# power_electronics6.net
KiCad netlist of a schematic drawn in EAGLE
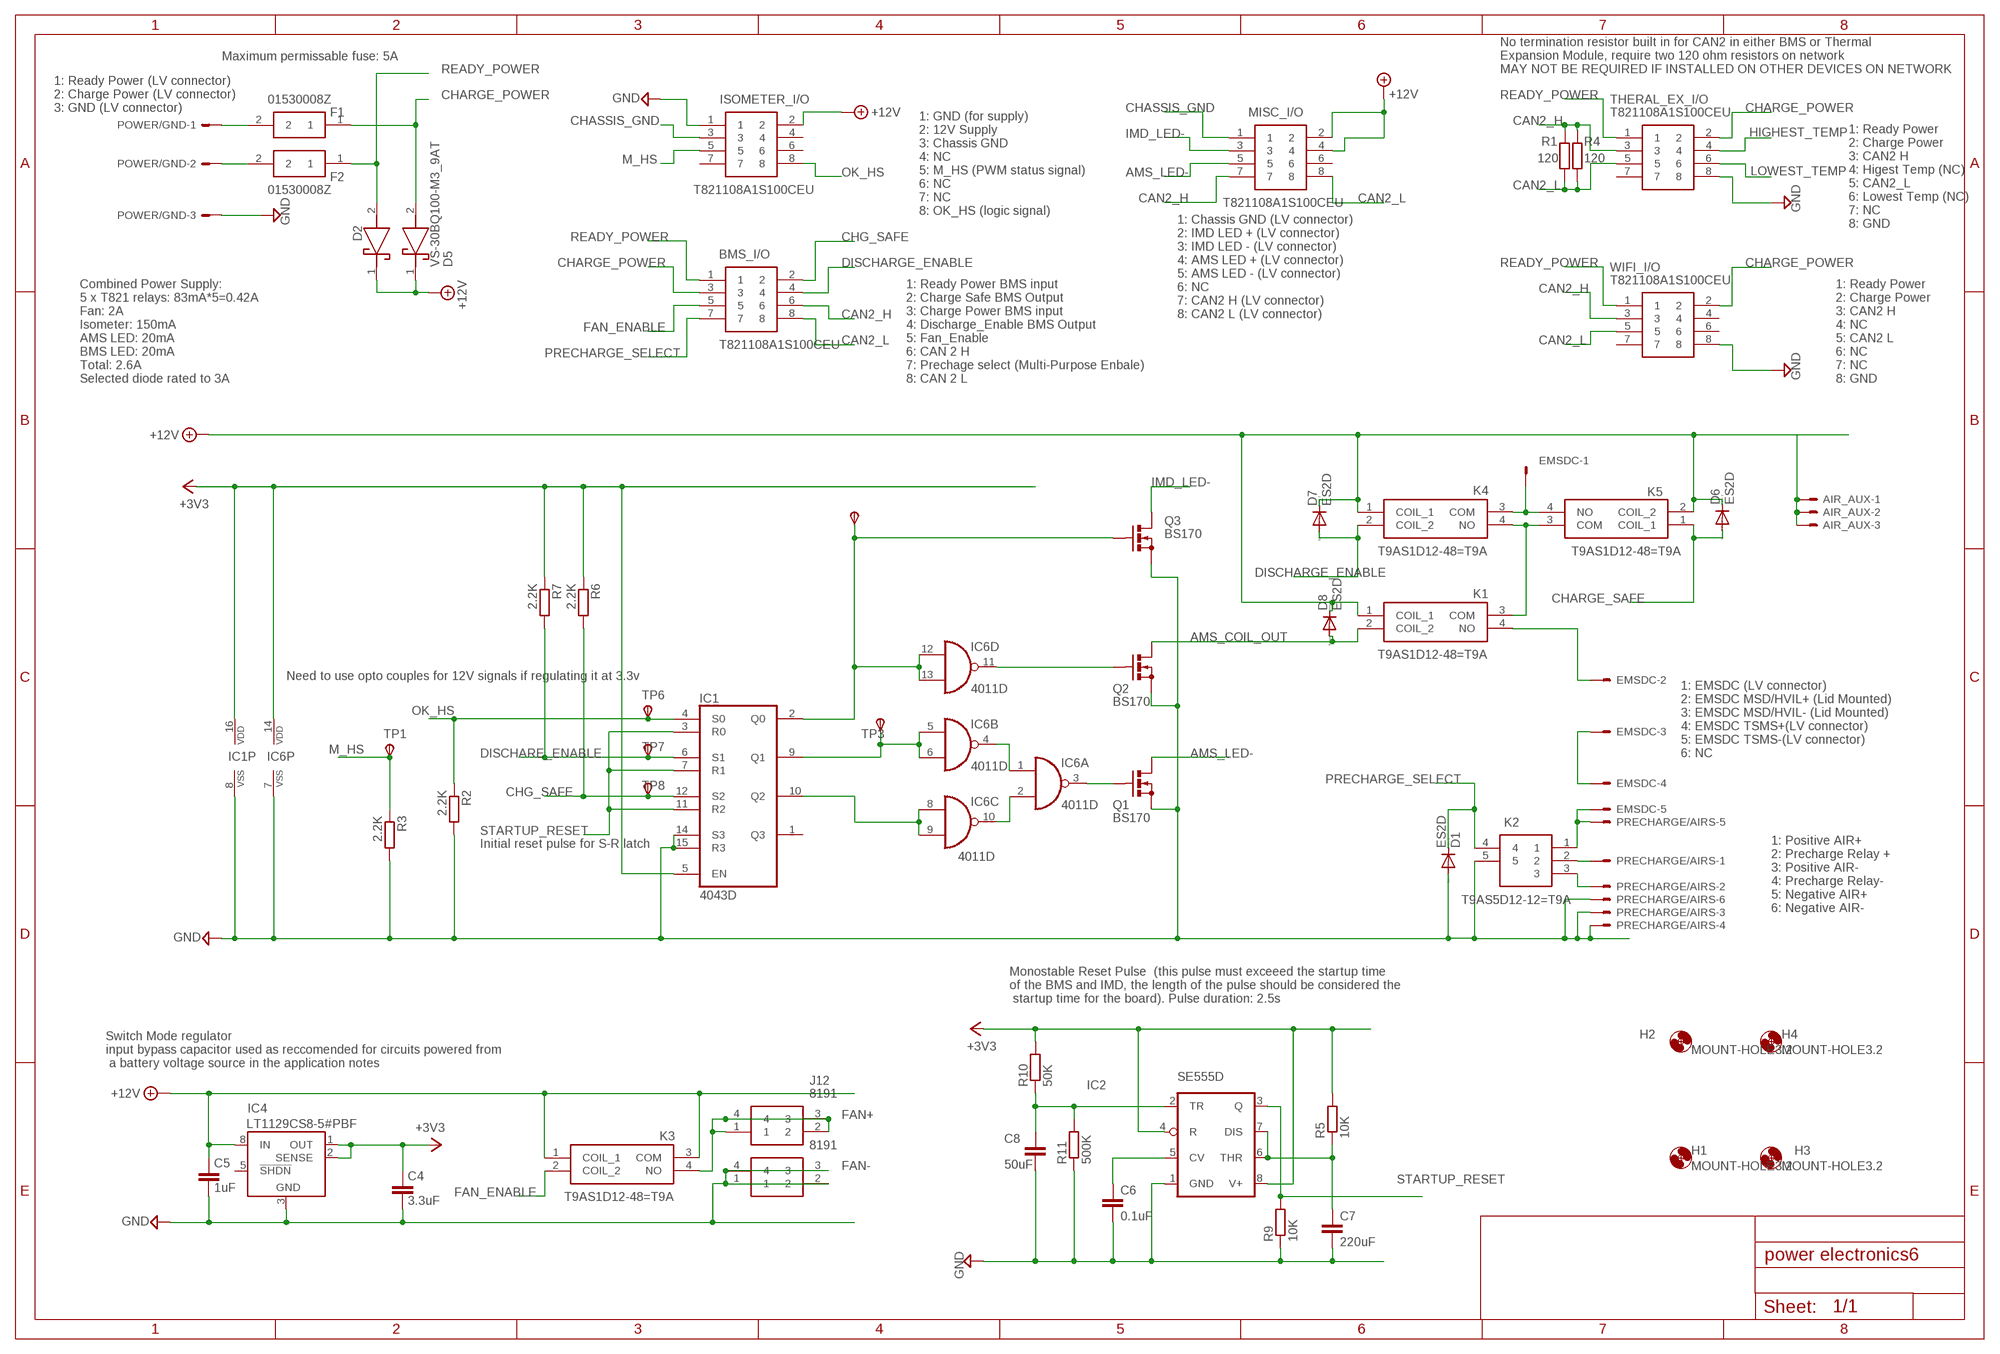
[diagram p0: schematic, sheet 1]

(export (version "E")
  (design (tool "Eeschema 10.0.6"))
  (components
    (comp (ref "AIR_AUX")
      (value "KK-156-3")
      (footprint "eagle-import:KK-156-3")
      (fields (field (name "MF") "MOLEX"))
      (libsource (lib "eagle-import") (part "KK-156-3"))
    )
    (comp (ref "BMS_I/O")
      (value "T821108A1S100CEU")
      (footprint "eagle-import:HDRV8W64P254_2X4_1778X895X915P")
      (fields (field (name "RS_PART_NUMBER") "8323569"))
      (libsource (lib "eagle-import") (part "T821108A1S100CEU"))
    )
    (comp (ref "C4")
      (value "3.3uF")
      (footprint "eagle-import:C1206")
      (libsource (lib "eagle-import") (part "C-EUC1206"))
    )
    (comp (ref "C5")
      (value "1uF")
      (footprint "eagle-import:C1206")
      (libsource (lib "eagle-import") (part "C-EUC1206"))
    )
    (comp (ref "C6")
      (value "0.1uF")
      (footprint "eagle-import:C1206")
      (libsource (lib "eagle-import") (part "C-EUC1206"))
    )
    (comp (ref "C7")
      (value "220uF")
      (footprint "eagle-import:C1206")
      (libsource (lib "eagle-import") (part "C-EUC1206"))
    )
    (comp (ref "C8")
      (value "50uF")
      (footprint "eagle-import:C1206")
      (libsource (lib "eagle-import") (part "C-EUC1206"))
    )
    (comp (ref "D1")
      (value "ES2D")
      (footprint "eagle-import:SMB")
      (libsource (lib "eagle-import") (part "ES2D"))
    )
    (comp (ref "D2")
      (value "VS-30BQ100-M3_9AT")
      (footprint "eagle-import:DIOM7959X262N")
      (fields
        (field (name "MANUFACTURER_PART_NUMBER") "VS-30BQ100-M3/9AT")
        (field (name "MOUSER_PART_NUMBER") "78-VS-30BQ100-M39AT")
      )
      (libsource (lib "eagle-import") (part "VS-30BQ100-M3_9AT"))
    )
    (comp (ref "D5")
      (value "VS-30BQ100-M3_9AT")
      (footprint "eagle-import:DIOM7959X262N")
      (fields
        (field (name "MANUFACTURER_PART_NUMBER") "VS-30BQ100-M3/9AT")
        (field (name "MOUSER_PART_NUMBER") "78-VS-30BQ100-M39AT")
      )
      (libsource (lib "eagle-import") (part "VS-30BQ100-M3_9AT"))
    )
    (comp (ref "D6")
      (value "ES2D")
      (footprint "eagle-import:SMB")
      (libsource (lib "eagle-import") (part "ES2D"))
    )
    (comp (ref "D7")
      (value "ES2D")
      (footprint "eagle-import:SMB")
      (libsource (lib "eagle-import") (part "ES2D"))
    )
    (comp (ref "D8")
      (value "ES2D")
      (footprint "eagle-import:SMB")
      (libsource (lib "eagle-import") (part "ES2D"))
    )
    (comp (ref "EMSDC")
      (value "KK-156-6")
      (footprint "eagle-import:KK-156-6")
      (fields (field (name "MF") "MOLEX"))
      (libsource (lib "eagle-import") (part "KK-156-6"))
    )
    (comp (ref "F1")
      (value "01530008Z")
      (footprint "eagle-import:01530008")
      (fields (field (name "RS_PART_NUMBER") "3607317"))
      (libsource (lib "eagle-import") (part "01530008Z"))
    )
    (comp (ref "F2")
      (value "01530008Z")
      (footprint "eagle-import:01530008")
      (fields (field (name "RS_PART_NUMBER") "3607317"))
      (libsource (lib "eagle-import") (part "01530008Z"))
    )
    (comp (ref "FAN-")
      (value "8191")
      (footprint "eagle-import:8191")
      (fields (field (name "MOUSER_PART_NUMBER") "534-8191") (field (name "RS_PART_NUMBER") "1194011"))
      (libsource (lib "eagle-import") (part "8191"))
    )
    (comp (ref "H1")
      (value "MOUNT-HOLE3.2")
      (footprint "eagle-import:3,2")
      (libsource (lib "eagle-import") (part "MOUNT-HOLE3.2"))
    )
    (comp (ref "H2")
      (value "MOUNT-HOLE3.2")
      (footprint "eagle-import:3,2")
      (libsource (lib "eagle-import") (part "MOUNT-HOLE3.2"))
    )
    (comp (ref "H3")
      (value "MOUNT-HOLE3.2")
      (footprint "eagle-import:3,2")
      (libsource (lib "eagle-import") (part "MOUNT-HOLE3.2"))
    )
    (comp (ref "H4")
      (value "MOUNT-HOLE3.2")
      (footprint "eagle-import:3,2")
      (libsource (lib "eagle-import") (part "MOUNT-HOLE3.2"))
    )
    (comp (ref "IC1")
      (value "4043D")
      (footprint "eagle-import:SO16")
      (libsource (lib "eagle-import") (part "4043D"))
    )
    (comp (ref "IC2")
      (value "SE555D")
      (footprint "eagle-import:SO08")
      (libsource (lib "eagle-import") (part "555DSE"))
    )
    (comp (ref "IC4")
      (value "LT1129CS8")
      (footprint "eagle-import:SOIC8")
      (fields (field (name "MPN") "LT1129CS8-5#PBF"))
      (libsource (lib "eagle-import") (part "LT1129CS8"))
    )
    (comp (ref "IC6")
      (value "4011D")
      (footprint "eagle-import:SO14")
      (libsource (lib "eagle-import") (part "4011D"))
    )
    (comp (ref "ISOMETER_I/O")
      (value "T821108A1S100CEU")
      (footprint "eagle-import:HDRV8W64P254_2X4_1778X895X915P")
      (fields (field (name "RS_PART_NUMBER") "8323569"))
      (libsource (lib "eagle-import") (part "T821108A1S100CEU"))
    )
    (comp (ref "J12")
      (value "8191")
      (footprint "eagle-import:8191")
      (fields (field (name "MOUSER_PART_NUMBER") "534-8191") (field (name "RS_PART_NUMBER") "1194011"))
      (libsource (lib "eagle-import") (part "8191"))
    )
    (comp (ref "K1")
      (value "T9AS1D12-48=T9A")
      (footprint "eagle-import:T9AS1D1248T9A")
      (fields (field (name "RS_PART_NUMBER") "6802534P"))
      (libsource (lib "eagle-import") (part "T9AS1D12-48=T9A"))
    )
    (comp (ref "K2")
      (value "T9AS5D12-12=T9A")
      (footprint "eagle-import:T9AS1D12")
      (fields (field (name "RS_PART_NUMBER") "6802528"))
      (libsource (lib "eagle-import") (part "T9AS5D12-12=T9A"))
    )
    (comp (ref "K3")
      (value "T9AS1D12-48=T9A")
      (footprint "eagle-import:T9AS1D1248T9A")
      (fields (field (name "RS_PART_NUMBER") "6802534P"))
      (libsource (lib "eagle-import") (part "T9AS1D12-48=T9A"))
    )
    (comp (ref "K4")
      (value "T9AS1D12-48=T9A")
      (footprint "eagle-import:T9AS1D1248T9A")
      (fields (field (name "RS_PART_NUMBER") "6802534P"))
      (libsource (lib "eagle-import") (part "T9AS1D12-48=T9A"))
    )
    (comp (ref "K5")
      (value "T9AS1D12-48=T9A")
      (footprint "eagle-import:T9AS1D1248T9A")
      (fields (field (name "RS_PART_NUMBER") "6802534P"))
      (libsource (lib "eagle-import") (part "T9AS1D12-48=T9A"))
    )
    (comp (ref "MISC_I/O")
      (value "T821108A1S100CEU")
      (footprint "eagle-import:HDRV8W64P254_2X4_1778X895X915P")
      (fields (field (name "RS_PART_NUMBER") "8323569"))
      (libsource (lib "eagle-import") (part "T821108A1S100CEU"))
    )
    (comp (ref "POWER/GND")
      (value "KK-156-3")
      (footprint "eagle-import:KK-156-3")
      (fields (field (name "MF") "MOLEX"))
      (libsource (lib "eagle-import") (part "KK-156-3"))
    )
    (comp (ref "PRECHARGE/AIRS")
      (value "KK-156-6")
      (footprint "eagle-import:KK-156-6")
      (fields (field (name "MF") "MOLEX"))
      (libsource (lib "eagle-import") (part "KK-156-6"))
    )
    (comp (ref "Q1")
      (value "BS170")
      (footprint "eagle-import:SOT54E")
      (libsource (lib "eagle-import") (part "BS170"))
    )
    (comp (ref "Q2")
      (value "BS170")
      (footprint "eagle-import:SOT54E")
      (libsource (lib "eagle-import") (part "BS170"))
    )
    (comp (ref "Q3")
      (value "BS170")
      (footprint "eagle-import:SOT54E")
      (libsource (lib "eagle-import") (part "BS170"))
    )
    (comp (ref "R1")
      (value "120")
      (footprint "eagle-import:R1206")
      (libsource (lib "eagle-import") (part "R-EU_R1206"))
    )
    (comp (ref "R2")
      (value "2.2K")
      (footprint "eagle-import:R1206")
      (libsource (lib "eagle-import") (part "R-EU_R1206"))
    )
    (comp (ref "R3")
      (value "2.2K")
      (footprint "eagle-import:R1206")
      (libsource (lib "eagle-import") (part "R-EU_R1206"))
    )
    (comp (ref "R4")
      (value "120")
      (footprint "eagle-import:R1206")
      (libsource (lib "eagle-import") (part "R-EU_R1206"))
    )
    (comp (ref "R5")
      (value "10K")
      (footprint "eagle-import:R1206")
      (libsource (lib "eagle-import") (part "R-EU_R1206"))
    )
    (comp (ref "R6")
      (value "2.2K")
      (footprint "eagle-import:R1206")
      (libsource (lib "eagle-import") (part "R-EU_R1206"))
    )
    (comp (ref "R7")
      (value "2.2K")
      (footprint "eagle-import:R1206")
      (libsource (lib "eagle-import") (part "R-EU_R1206"))
    )
    (comp (ref "R9")
      (value "10K")
      (footprint "eagle-import:R1206")
      (libsource (lib "eagle-import") (part "R-EU_R1206"))
    )
    (comp (ref "R10")
      (value "50K")
      (footprint "eagle-import:R1206")
      (libsource (lib "eagle-import") (part "R-EU_R1206"))
    )
    (comp (ref "R11")
      (value "500K")
      (footprint "eagle-import:R1206")
      (libsource (lib "eagle-import") (part "R-EU_R1206"))
    )
    (comp (ref "THERAL_EX_I/O")
      (value "T821108A1S100CEU")
      (footprint "eagle-import:HDRV8W64P254_2X4_1778X895X915P")
      (fields (field (name "RS_PART_NUMBER") "8323569"))
      (libsource (lib "eagle-import") (part "T821108A1S100CEU"))
    )
    (comp (ref "TP1")
      (value "TPSPAD1-17")
      (footprint "eagle-import:P1-17")
      (libsource (lib "eagle-import") (part "TPSPAD1-17"))
    )
    (comp (ref "TP2")
      (value "TPSPAD1-17")
      (footprint "eagle-import:P1-17")
      (libsource (lib "eagle-import") (part "TPSPAD1-17"))
    )
    (comp (ref "TP3")
      (value "TPSPAD1-17")
      (footprint "eagle-import:P1-17")
      (libsource (lib "eagle-import") (part "TPSPAD1-17"))
    )
    (comp (ref "TP6")
      (value "TPSPAD1-17")
      (footprint "eagle-import:P1-17")
      (libsource (lib "eagle-import") (part "TPSPAD1-17"))
    )
    (comp (ref "TP7")
      (value "TPSPAD1-17")
      (footprint "eagle-import:P1-17")
      (libsource (lib "eagle-import") (part "TPSPAD1-17"))
    )
    (comp (ref "TP8")
      (value "TPSPAD1-17")
      (footprint "eagle-import:P1-17")
      (libsource (lib "eagle-import") (part "TPSPAD1-17"))
    )
    (comp (ref "WIFI_I/O")
      (value "T821108A1S100CEU")
      (footprint "eagle-import:HDRV8W64P254_2X4_1778X895X915P")
      (fields (field (name "RS_PART_NUMBER") "8323569"))
      (libsource (lib "eagle-import") (part "T821108A1S100CEU"))
    )
  )
  (nets
    (net (code "1") (name "+3V3") (class "Default")
      (node (ref "C4") (pin "1") (pinfunction "1_1") (pintype "passive"))
      (node (ref "IC1") (pin "16") (pinfunction "VDD_16") (pintype "power_in"))
      (node (ref "IC1") (pin "5") (pinfunction "EN_5") (pintype "input"))
      (node (ref "IC2") (pin "4") (pinfunction "R_4") (pintype "input"))
      (node (ref "IC2") (pin "8") (pinfunction "V+_8") (pintype "power_in"))
      (node (ref "IC4") (pin "1") (pinfunction "OUT_1") (pintype "output"))
      (node (ref "IC4") (pin "2") (pinfunction "SENSE_2") (pintype "input"))
      (node (ref "IC6") (pin "14") (pinfunction "VDD_14") (pintype "power_in"))
      (node (ref "R10") (pin "2") (pinfunction "2_2") (pintype "passive"))
      (node (ref "R5") (pin "2") (pinfunction "2_2") (pintype "passive"))
      (node (ref "R6") (pin "1") (pinfunction "1_1") (pintype "passive"))
      (node (ref "R7") (pin "1") (pinfunction "1_1") (pintype "passive"))
    )
    (net (code "2") (name "+12V") (class "Default")
      (node (ref "AIR_AUX") (pin "1") (pinfunction "S_1") (pintype "passive"))
      (node (ref "AIR_AUX") (pin "2") (pinfunction "S_2") (pintype "passive"))
      (node (ref "AIR_AUX") (pin "3") (pinfunction "S_3") (pintype "passive"))
      (node (ref "C5") (pin "1") (pinfunction "1_1") (pintype "passive"))
      (node (ref "D2") (pin "1") (pinfunction "K_1") (pintype "bidirectional"))
      (node (ref "D5") (pin "1") (pinfunction "K_1") (pintype "bidirectional"))
      (node (ref "D6") (pin "C") (pinfunction "C_C") (pintype "passive"))
      (node (ref "D7") (pin "C") (pinfunction "C_C") (pintype "passive"))
      (node (ref "D8") (pin "C") (pinfunction "C_C") (pintype "passive"))
      (node (ref "IC4") (pin "8") (pinfunction "IN_8") (pintype "input"))
      (node (ref "ISOMETER_I/O") (pin "2") (pinfunction "2_2") (pintype "bidirectional"))
      (node (ref "K1") (pin "1") (pinfunction "COIL_1_1") (pintype "bidirectional"))
      (node (ref "K3") (pin "1") (pinfunction "COIL_1_1") (pintype "bidirectional"))
      (node (ref "K3") (pin "3") (pinfunction "COM_3") (pintype "bidirectional"))
      (node (ref "K4") (pin "1") (pinfunction "COIL_1_1") (pintype "bidirectional"))
      (node (ref "K5") (pin "2") (pinfunction "COIL_2_2") (pintype "bidirectional"))
      (node (ref "MISC_I/O") (pin "2") (pinfunction "2_2") (pintype "bidirectional"))
      (node (ref "MISC_I/O") (pin "4") (pinfunction "4_4") (pintype "bidirectional"))
    )
    (net (code "3") (name "/AMS_COIL_OUT") (class "Default")
      (node (ref "D8") (pin "A") (pinfunction "A_A") (pintype "passive"))
      (node (ref "K1") (pin "2") (pinfunction "COIL_2_2") (pintype "bidirectional"))
      (node (ref "Q2") (pin "D") (pinfunction "D_D") (pintype "passive"))
    )
    (net (code "4") (name "/AMS_LED-") (class "Default")
      (node (ref "MISC_I/O") (pin "5") (pinfunction "5_5") (pintype "bidirectional"))
      (node (ref "Q1") (pin "D") (pinfunction "D_D") (pintype "passive"))
    )
    (net (code "5") (name "/CAN2_H") (class "Default")
      (node (ref "BMS_I/O") (pin "6") (pinfunction "6_6") (pintype "bidirectional"))
      (node (ref "MISC_I/O") (pin "7") (pinfunction "7_7") (pintype "bidirectional"))
      (node (ref "R1") (pin "1") (pinfunction "1_1") (pintype "passive"))
      (node (ref "R4") (pin "1") (pinfunction "1_1") (pintype "passive"))
      (node (ref "THERAL_EX_I/O") (pin "3") (pinfunction "3_3") (pintype "bidirectional"))
      (node (ref "WIFI_I/O") (pin "3") (pinfunction "3_3") (pintype "bidirectional"))
    )
    (net (code "6") (name "/CAN2_L") (class "Default")
      (node (ref "BMS_I/O") (pin "8") (pinfunction "8_8") (pintype "bidirectional"))
      (node (ref "MISC_I/O") (pin "8") (pinfunction "8_8") (pintype "bidirectional"))
      (node (ref "R1") (pin "2") (pinfunction "2_2") (pintype "passive"))
      (node (ref "R4") (pin "2") (pinfunction "2_2") (pintype "passive"))
      (node (ref "THERAL_EX_I/O") (pin "5") (pinfunction "5_5") (pintype "bidirectional"))
      (node (ref "WIFI_I/O") (pin "5") (pinfunction "5_5") (pintype "bidirectional"))
    )
    (net (code "7") (name "/CHARGE_POWER") (class "Default")
      (node (ref "BMS_I/O") (pin "3") (pinfunction "3_3") (pintype "bidirectional"))
      (node (ref "D5") (pin "2") (pinfunction "A_2") (pintype "bidirectional"))
      (node (ref "F1") (pin "1") (pinfunction "1_1") (pintype "bidirectional"))
      (node (ref "THERAL_EX_I/O") (pin "2") (pinfunction "2_2") (pintype "bidirectional"))
      (node (ref "WIFI_I/O") (pin "2") (pinfunction "2_2") (pintype "bidirectional"))
    )
    (net (code "8") (name "/CHARGE_SAFE") (class "Default")
      (node (ref "D6") (pin "A") (pinfunction "A_A") (pintype "passive"))
      (node (ref "K5") (pin "1") (pinfunction "COIL_1_1") (pintype "bidirectional"))
    )
    (net (code "9") (name "/CHASSIS_GND") (class "Default")
      (node (ref "ISOMETER_I/O") (pin "3") (pinfunction "3_3") (pintype "bidirectional"))
      (node (ref "MISC_I/O") (pin "1") (pinfunction "1_1") (pintype "bidirectional"))
    )
    (net (code "10") (name "/CHG_SAFE") (class "Default")
      (node (ref "BMS_I/O") (pin "2") (pinfunction "2_2") (pintype "bidirectional"))
      (node (ref "IC1") (pin "12") (pinfunction "S2_12") (pintype "input"))
      (node (ref "R6") (pin "2") (pinfunction "2_2") (pintype "passive"))
      (node (ref "TP8") (pin "TP") (pinfunction "PP_TP") (pintype "input"))
    )
    (net (code "11") (name "/DISCHARE_ENABLE") (class "Default")
      (node (ref "IC1") (pin "6") (pinfunction "S1_6") (pintype "input"))
      (node (ref "R7") (pin "2") (pinfunction "2_2") (pintype "passive"))
      (node (ref "TP7") (pin "TP") (pinfunction "PP_TP") (pintype "input"))
    )
    (net (code "12") (name "/DISCHARGE_ENABLE") (class "Default")
      (node (ref "BMS_I/O") (pin "4") (pinfunction "4_4") (pintype "bidirectional"))
      (node (ref "D7") (pin "A") (pinfunction "A_A") (pintype "passive"))
      (node (ref "K4") (pin "2") (pinfunction "COIL_2_2") (pintype "bidirectional"))
    )
    (net (code "13") (name "/FAN+") (class "Default")
      (node (ref "J12") (pin "1") (pinfunction "1_1") (pintype "bidirectional"))
      (node (ref "J12") (pin "2") (pinfunction "2_2") (pintype "bidirectional"))
      (node (ref "J12") (pin "3") (pinfunction "3_3") (pintype "bidirectional"))
      (node (ref "J12") (pin "4") (pinfunction "4_4") (pintype "bidirectional"))
      (node (ref "K3") (pin "4") (pinfunction "NO_4") (pintype "bidirectional"))
    )
    (net (code "14") (name "/FAN_ENABLE") (class "Default")
      (node (ref "BMS_I/O") (pin "5") (pinfunction "5_5") (pintype "bidirectional"))
      (node (ref "K3") (pin "2") (pinfunction "COIL_2_2") (pintype "bidirectional"))
    )
    (net (code "15") (name "/HIGHEST_TEMP") (class "Default")
      (node (ref "THERAL_EX_I/O") (pin "4") (pinfunction "4_4") (pintype "bidirectional"))
    )
    (net (code "16") (name "/IMD_LED-") (class "Default")
      (node (ref "MISC_I/O") (pin "3") (pinfunction "3_3") (pintype "bidirectional"))
      (node (ref "Q3") (pin "D") (pinfunction "D_D") (pintype "passive"))
    )
    (net (code "17") (name "/LOWEST_TEMP") (class "Default")
      (node (ref "THERAL_EX_I/O") (pin "6") (pinfunction "6_6") (pintype "bidirectional"))
    )
    (net (code "18") (name "/M_HS") (class "Default")
      (node (ref "ISOMETER_I/O") (pin "5") (pinfunction "5_5") (pintype "bidirectional"))
      (node (ref "R3") (pin "1") (pinfunction "1_1") (pintype "passive"))
      (node (ref "TP1") (pin "TP") (pinfunction "PP_TP") (pintype "input"))
    )
    (net (code "19") (name "/OK_HS") (class "Default")
      (node (ref "IC1") (pin "4") (pinfunction "S0_4") (pintype "input"))
      (node (ref "ISOMETER_I/O") (pin "8") (pinfunction "8_8") (pintype "bidirectional"))
      (node (ref "R2") (pin "1") (pinfunction "1_1") (pintype "passive"))
      (node (ref "TP6") (pin "TP") (pinfunction "PP_TP") (pintype "input"))
    )
    (net (code "20") (name "/PRECHARGE_SELECT") (class "Default")
      (node (ref "BMS_I/O") (pin "7") (pinfunction "7_7") (pintype "bidirectional"))
      (node (ref "D1") (pin "C") (pinfunction "C_C") (pintype "passive"))
      (node (ref "K2") (pin "4") (pinfunction "4_4") (pintype "bidirectional"))
    )
    (net (code "21") (name "/READY_POWER") (class "Default")
      (node (ref "BMS_I/O") (pin "1") (pinfunction "1_1") (pintype "bidirectional"))
      (node (ref "D2") (pin "2") (pinfunction "A_2") (pintype "bidirectional"))
      (node (ref "F2") (pin "1") (pinfunction "1_1") (pintype "bidirectional"))
      (node (ref "THERAL_EX_I/O") (pin "1") (pinfunction "1_1") (pintype "bidirectional"))
      (node (ref "WIFI_I/O") (pin "1") (pinfunction "1_1") (pintype "bidirectional"))
    )
    (net (code "22") (name "/STARTUP_RESET") (class "Default")
      (node (ref "IC1") (pin "11") (pinfunction "R2_11") (pintype "input"))
      (node (ref "IC1") (pin "3") (pinfunction "R0_3") (pintype "input"))
      (node (ref "IC1") (pin "7") (pinfunction "R1_7") (pintype "input"))
      (node (ref "IC2") (pin "3") (pinfunction "Q_3") (pintype "output"))
      (node (ref "R9") (pin "2") (pinfunction "2_2") (pintype "passive"))
    )
    (net (code "23") (name "GND") (class "Default")
      (node (ref "C4") (pin "2") (pinfunction "2_2") (pintype "passive"))
      (node (ref "C5") (pin "2") (pinfunction "2_2") (pintype "passive"))
      (node (ref "C6") (pin "2") (pinfunction "2_2") (pintype "passive"))
      (node (ref "C7") (pin "2") (pinfunction "2_2") (pintype "passive"))
      (node (ref "C8") (pin "2") (pinfunction "2_2") (pintype "passive"))
      (node (ref "D1") (pin "A") (pinfunction "A_A") (pintype "passive"))
      (node (ref "FAN-") (pin "1") (pinfunction "1_1") (pintype "bidirectional"))
      (node (ref "FAN-") (pin "2") (pinfunction "2_2") (pintype "bidirectional"))
      (node (ref "FAN-") (pin "3") (pinfunction "3_3") (pintype "bidirectional"))
      (node (ref "FAN-") (pin "4") (pinfunction "4_4") (pintype "bidirectional"))
      (node (ref "IC1") (pin "14") (pinfunction "S3_14") (pintype "input"))
      (node (ref "IC1") (pin "15") (pinfunction "R3_15") (pintype "input"))
      (node (ref "IC1") (pin "8") (pinfunction "VSS_8") (pintype "power_in"))
      (node (ref "IC2") (pin "1") (pinfunction "GND_1") (pintype "power_in"))
      (node (ref "IC4") (pin "3") (pinfunction "GND_3") (pintype "power_in"))
      (node (ref "IC6") (pin "7") (pinfunction "VSS_7") (pintype "power_in"))
      (node (ref "ISOMETER_I/O") (pin "1") (pinfunction "1_1") (pintype "bidirectional"))
      (node (ref "K2") (pin "5") (pinfunction "5_5") (pintype "bidirectional"))
      (node (ref "POWER/GND") (pin "3") (pinfunction "S_3") (pintype "passive"))
      (node (ref "PRECHARGE/AIRS") (pin "3") (pinfunction "S_3") (pintype "passive"))
      (node (ref "PRECHARGE/AIRS") (pin "4") (pinfunction "S_4") (pintype "passive"))
      (node (ref "PRECHARGE/AIRS") (pin "6") (pinfunction "S_6") (pintype "passive"))
      (node (ref "Q1") (pin "S") (pinfunction "S_S") (pintype "passive"))
      (node (ref "Q2") (pin "S") (pinfunction "S_S") (pintype "passive"))
      (node (ref "Q3") (pin "S") (pinfunction "S_S") (pintype "passive"))
      (node (ref "R11") (pin "1") (pinfunction "1_1") (pintype "passive"))
      (node (ref "R2") (pin "2") (pinfunction "2_2") (pintype "passive"))
      (node (ref "R3") (pin "2") (pinfunction "2_2") (pintype "passive"))
      (node (ref "R9") (pin "1") (pinfunction "1_1") (pintype "passive"))
      (node (ref "THERAL_EX_I/O") (pin "8") (pinfunction "8_8") (pintype "bidirectional"))
      (node (ref "WIFI_I/O") (pin "8") (pinfunction "8_8") (pintype "bidirectional"))
    )
    (net (code "24") (name "Net-(EMSDCA-S)") (class "Default")
      (node (ref "EMSDC") (pin "1") (pinfunction "S_1") (pintype "passive"))
      (node (ref "K4") (pin "3") (pinfunction "COM_3") (pintype "bidirectional"))
      (node (ref "K5") (pin "4") (pinfunction "NO_4") (pintype "bidirectional"))
    )
    (net (code "25") (name "Net-(EMSDCB-S)") (class "Default")
      (node (ref "EMSDC") (pin "2") (pinfunction "S_2") (pintype "passive"))
      (node (ref "K1") (pin "4") (pinfunction "NO_4") (pintype "bidirectional"))
    )
    (net (code "26") (name "Net-(EMSDCC-S)") (class "Default")
      (node (ref "EMSDC") (pin "3") (pinfunction "S_3") (pintype "passive"))
      (node (ref "EMSDC") (pin "4") (pinfunction "S_4") (pintype "passive"))
    )
    (net (code "27") (name "Net-(EMSDCE-S)") (class "Default")
      (node (ref "EMSDC") (pin "5") (pinfunction "S_5") (pintype "passive"))
      (node (ref "K2") (pin "1") (pinfunction "1_1") (pintype "bidirectional"))
      (node (ref "PRECHARGE/AIRS") (pin "5") (pinfunction "S_5") (pintype "passive"))
    )
    (net (code "28") (name "Net-(IC1A-Q0)") (class "Default")
      (node (ref "IC1") (pin "2") (pinfunction "Q0_2") (pintype "output"))
      (node (ref "IC6") (pin "12") (pinfunction "I0_12") (pintype "input"))
      (node (ref "IC6") (pin "13") (pinfunction "I1_13") (pintype "input"))
      (node (ref "Q3") (pin "G") (pinfunction "G_G") (pintype "passive"))
      (node (ref "TP2") (pin "TP") (pinfunction "PP_TP") (pintype "input"))
    )
    (net (code "29") (name "Net-(IC1A-Q1)") (class "Default")
      (node (ref "IC1") (pin "9") (pinfunction "Q1_9") (pintype "output"))
      (node (ref "IC6") (pin "5") (pinfunction "I0_5") (pintype "input"))
      (node (ref "IC6") (pin "6") (pinfunction "I1_6") (pintype "input"))
      (node (ref "TP3") (pin "TP") (pinfunction "PP_TP") (pintype "input"))
    )
    (net (code "30") (name "Net-(IC1A-Q2)") (class "Default")
      (node (ref "IC1") (pin "10") (pinfunction "Q2_10") (pintype "output"))
      (node (ref "IC6") (pin "8") (pinfunction "I0_8") (pintype "input"))
      (node (ref "IC6") (pin "9") (pinfunction "I1_9") (pintype "input"))
    )
    (net (code "31") (name "Net-(IC2-CV)") (class "Default")
      (node (ref "C6") (pin "1") (pinfunction "1_1") (pintype "passive"))
      (node (ref "IC2") (pin "5") (pinfunction "CV_5") (pintype "input"))
    )
    (net (code "32") (name "Net-(IC2-DIS)") (class "Default")
      (node (ref "C7") (pin "1") (pinfunction "1_1") (pintype "passive"))
      (node (ref "IC2") (pin "6") (pinfunction "THR_6") (pintype "input"))
      (node (ref "IC2") (pin "7") (pinfunction "DIS_7") (pintype "input"))
      (node (ref "R5") (pin "1") (pinfunction "1_1") (pintype "passive"))
    )
    (net (code "33") (name "Net-(IC2-TR)") (class "Default")
      (node (ref "C8") (pin "1") (pinfunction "1_1") (pintype "passive"))
      (node (ref "IC2") (pin "2") (pinfunction "TR_2") (pintype "input"))
      (node (ref "R10") (pin "1") (pinfunction "1_1") (pintype "passive"))
      (node (ref "R11") (pin "2") (pinfunction "2_2") (pintype "passive"))
    )
    (net (code "34") (name "Net-(IC6A-I0)") (class "Default")
      (node (ref "IC6") (pin "1") (pinfunction "I0_1") (pintype "input"))
      (node (ref "IC6") (pin "4") (pinfunction "O_4") (pintype "output"))
    )
    (net (code "35") (name "Net-(IC6A-I1)") (class "Default")
      (node (ref "IC6") (pin "10") (pinfunction "O_10") (pintype "output"))
      (node (ref "IC6") (pin "2") (pinfunction "I1_2") (pintype "input"))
    )
    (net (code "36") (name "Net-(IC6A-O)") (class "Default")
      (node (ref "IC6") (pin "3") (pinfunction "O_3") (pintype "output"))
      (node (ref "Q1") (pin "G") (pinfunction "G_G") (pintype "passive"))
    )
    (net (code "37") (name "Net-(IC6D-O)") (class "Default")
      (node (ref "IC6") (pin "11") (pinfunction "O_11") (pintype "output"))
      (node (ref "Q2") (pin "G") (pinfunction "G_G") (pintype "passive"))
    )
    (net (code "38") (name "Net-(K1-COM)") (class "Default")
      (node (ref "K1") (pin "3") (pinfunction "COM_3") (pintype "bidirectional"))
      (node (ref "K4") (pin "4") (pinfunction "NO_4") (pintype "bidirectional"))
      (node (ref "K5") (pin "3") (pinfunction "COM_3") (pintype "bidirectional"))
    )
    (net (code "39") (name "Net-(POWER/GNDA-S)") (class "Default")
      (node (ref "F1") (pin "2") (pinfunction "2_2") (pintype "bidirectional"))
      (node (ref "POWER/GND") (pin "1") (pinfunction "S_1") (pintype "passive"))
    )
    (net (code "40") (name "Net-(POWER/GNDB-S)") (class "Default")
      (node (ref "F2") (pin "2") (pinfunction "2_2") (pintype "bidirectional"))
      (node (ref "POWER/GND") (pin "2") (pinfunction "S_2") (pintype "passive"))
    )
    (net (code "41") (name "Net-(PRECHARGE/AIRSA-S)") (class "Default")
      (node (ref "K2") (pin "2") (pinfunction "2_2") (pintype "bidirectional"))
      (node (ref "PRECHARGE/AIRS") (pin "1") (pinfunction "S_1") (pintype "passive"))
    )
    (net (code "42") (name "Net-(PRECHARGE/AIRSB-S)") (class "Default")
      (node (ref "K2") (pin "3") (pinfunction "3_3") (pintype "bidirectional"))
      (node (ref "PRECHARGE/AIRS") (pin "2") (pinfunction "S_2") (pintype "passive"))
    )
    (net (code "43") (name "unconnected-(IC1A-Q3-Pad1)") (class "Default")
      (node (ref "IC1") (pin "1") (pinfunction "Q3_1") (pintype "output"))
    )
    (net (code "44") (name "unconnected-(IC4A-~{SHDN}-Pad5)") (class "Default")
      (node (ref "IC4") (pin "5") (pinfunction "~{SHDN}_5") (pintype "input"))
    )
    (net (code "45") (name "unconnected-(ISOMETER_I/O-Pad4)") (class "Default")
      (node (ref "ISOMETER_I/O") (pin "4") (pinfunction "4_4") (pintype "bidirectional"))
    )
    (net (code "46") (name "unconnected-(ISOMETER_I/O-Pad6)") (class "Default")
      (node (ref "ISOMETER_I/O") (pin "6") (pinfunction "6_6") (pintype "bidirectional"))
    )
    (net (code "47") (name "unconnected-(ISOMETER_I/O-Pad7)") (class "Default")
      (node (ref "ISOMETER_I/O") (pin "7") (pinfunction "7_7") (pintype "bidirectional"))
    )
    (net (code "48") (name "unconnected-(MISC_I/O-Pad6)") (class "Default")
      (node (ref "MISC_I/O") (pin "6") (pinfunction "6_6") (pintype "bidirectional"))
    )
    (net (code "49") (name "unconnected-(THERAL_EX_I/O-Pad7)") (class "Default")
      (node (ref "THERAL_EX_I/O") (pin "7") (pinfunction "7_7") (pintype "bidirectional"))
    )
    (net (code "50") (name "unconnected-(WIFI_I/O-Pad4)") (class "Default")
      (node (ref "WIFI_I/O") (pin "4") (pinfunction "4_4") (pintype "bidirectional"))
    )
    (net (code "51") (name "unconnected-(WIFI_I/O-Pad6)") (class "Default")
      (node (ref "WIFI_I/O") (pin "6") (pinfunction "6_6") (pintype "bidirectional"))
    )
    (net (code "52") (name "unconnected-(WIFI_I/O-Pad7)") (class "Default")
      (node (ref "WIFI_I/O") (pin "7") (pinfunction "7_7") (pintype "bidirectional"))
    )
  )
)
